# Force_Plates_Power_Supply.net
KiCad netlist of a schematic drawn in Altium Designer
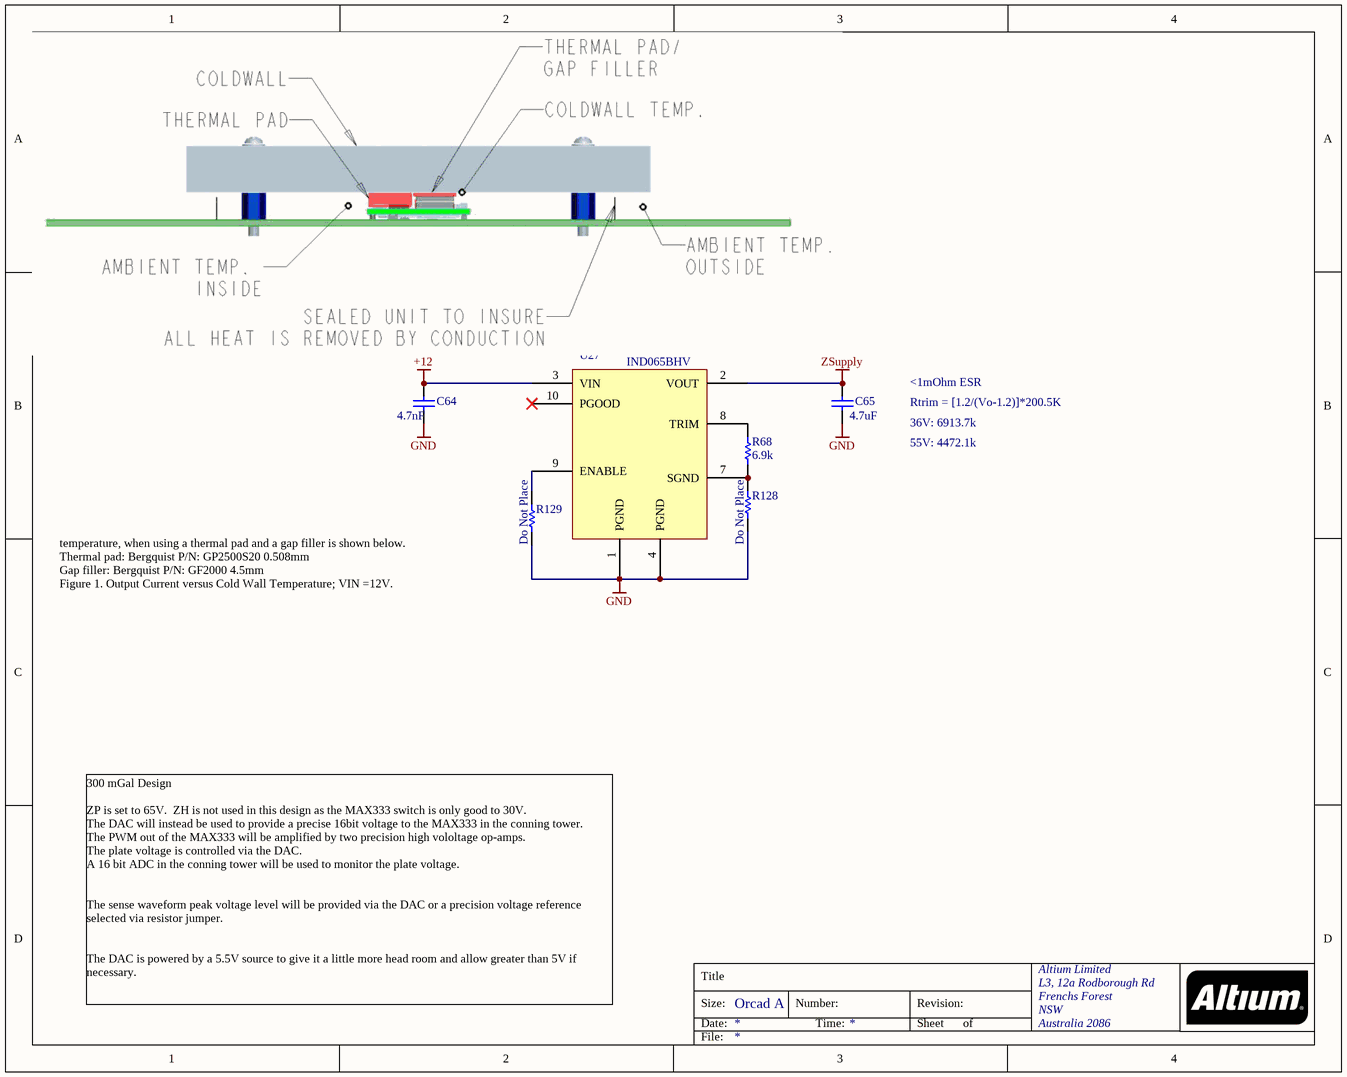
[diagram p0: Force_Plates_Power_Supply.SchDoc]

(export (version "E")
  (design (tool "Eeschema 10.0.6"))
  (components
    (comp (ref "C64")
      (value "C1206C472K1RECAUTO")
      (footprint "CAPC0805(2012)155_L")
      (description "4700pF ±10% 100V Ceramic Capacitor X7R 1206 (3216 Metric)")
      (fields
        (field (name "MANUFACTURER") "KEMET")
        (field (name "CAPACITANCE") "4.7nF")
        (field (name "TOLERANCE") "10%")
      )
      (libsource (lib "Altium Content Vault") (part "CMP-1036-04882-1"))
    )
    (comp (ref "C65")
      (value "C1206C472K1RECAUTO")
      (footprint "CAPC1210(3225)130_M")
      (description "4700pF ±10% 100V Ceramic Capacitor X7R 1206 (3216 Metric)")
      (fields (field (name "MANUFACTURER") "KEMET") (field (name "CAPACITANCE") "4.7uF"))
      (libsource (lib "Altium Content Vault") (part "CMP-1038-00936-1"))
    )
    (comp (ref "R68")
      (value "6.9k")
      (footprint "RESC0805(2012)_L")
      (description "6.9 kOhms ±0.1% 0.1W,0805")
      (fields
        (field (name "MANUFACTURER") "Vishay Dale")
        (field (name "MANUFACTURER PART NUMBER") "CRCW080510K0FKEA")
      )
      (libsource (lib "Altium Content Vault") (part "CMP-1013-00215-1"))
    )
    (comp (ref "R128")
      (value "Do Not Place")
      (footprint "RESC0805(2012)_L")
      (description "0 Ohms ±0.1% 0.1W,0805")
      (fields
        (field (name "MANUFACTURER") "Vishay Dale")
        (field (name "MANUFACTURER PART NUMBER") "CRCW080510K0FKEA")
      )
      (libsource (lib "Altium Content Vault") (part "CMP-1013-00215-1"))
    )
    (comp (ref "R129")
      (value "Do Not Place")
      (footprint "RESC0805(2012)_L")
      (description "0 Ohms ±0.1% 0.1W,0805")
      (fields
        (field (name "MANUFACTURER") "Vishay Dale")
        (field (name "MANUFACTURER PART NUMBER") "CRCW080510K0FKEA")
      )
      (libsource (lib "Altium Content Vault") (part "CMP-1013-00215-1"))
    )
    (comp (ref "U27")
      (value "IND065BHV")
      (footprint "IND065BHV")
      (description "Non-Isolated PoL Module DC DC Converter 1 Output 32 ~ 54V 2A 9.6V - 14.4V Input")
      (libsource (lib "ZLS_Schematic_lib") (part "IND065BHV"))
    )
  )
  (nets
    (net (code "1") (name "+12") (class "Default")
      (node (ref "C64") (pin "2") (pinfunction "2_2") (pintype "passive"))
      (node (ref "U27") (pin "3") (pinfunction "VIN_3") (pintype "passive"))
    )
    (net (code "2") (name "GND") (class "Default")
      (node (ref "C64") (pin "1") (pinfunction "1_1") (pintype "passive"))
      (node (ref "C65") (pin "1") (pinfunction "1_1") (pintype "passive"))
      (node (ref "R128") (pin "2") (pinfunction "2_2") (pintype "passive"))
      (node (ref "R129") (pin "2") (pinfunction "2_2") (pintype "passive"))
      (node (ref "U27") (pin "1") (pinfunction "PGND_1") (pintype "passive"))
      (node (ref "U27") (pin "4") (pinfunction "PGND_4") (pintype "passive"))
    )
    (net (code "3") (name "Net-(U27-ENABLE)") (class "Default")
      (node (ref "R129") (pin "1") (pinfunction "1_1") (pintype "passive"))
      (node (ref "U27") (pin "9") (pinfunction "ENABLE_9") (pintype "passive"))
    )
    (net (code "4") (name "Net-(U27-SGND)") (class "Default")
      (node (ref "R128") (pin "1") (pinfunction "1_1") (pintype "passive"))
      (node (ref "R68") (pin "2") (pinfunction "2_2") (pintype "passive"))
      (node (ref "U27") (pin "7") (pinfunction "SGND_7") (pintype "passive"))
    )
    (net (code "5") (name "Net-(U27-TRIM)") (class "Default")
      (node (ref "R68") (pin "1") (pinfunction "1_1") (pintype "passive"))
      (node (ref "U27") (pin "8") (pinfunction "TRIM_8") (pintype "passive"))
    )
    (net (code "6") (name "ZSupply") (class "Default")
      (node (ref "C65") (pin "2") (pinfunction "2_2") (pintype "passive"))
      (node (ref "U27") (pin "2") (pinfunction "VOUT_2") (pintype "passive"))
    )
    (net (code "7") (name "unconnected-(U27-PGOOD-Pad10)") (class "Default")
      (node (ref "U27") (pin "10") (pinfunction "PGOOD_10") (pintype "passive+no_connect"))
    )
  )
)
